# Antenna_Board_v4_3.net
KiCad netlist of a schematic drawn in EAGLE
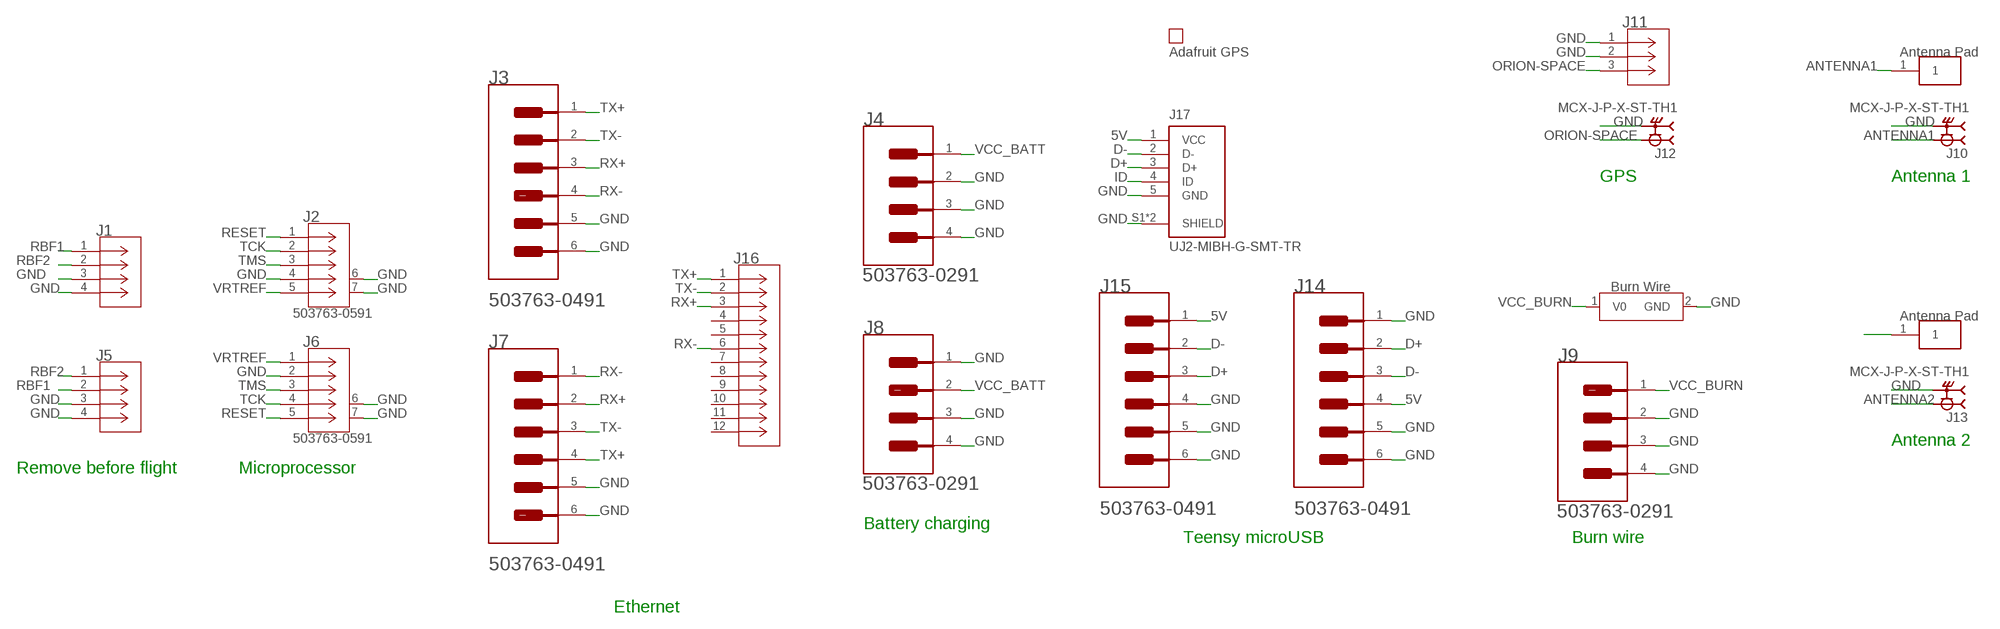
[diagram p0: schematic, sheet 1]

(export (version "E")
  (design (tool "Eeschema 10.0.6"))
  (components
    (comp (ref "GPS")
      (value "PA1010D")
      (footprint "eagle-import:PA1010D")
      (libsource (lib "eagle-import") (part "PA1010D"))
    )
    (comp (ref "J1")
      (value "5037630291")
      (footprint "eagle-import:CON_5037630291")
      (fields (field (name "COPYRIGHT") "Copyright (C) 2018 Accelerated Designs. All rights reserved"))
      (libsource (lib "eagle-import") (part "5037630291"))
    )
    (comp (ref "J2")
      (value "503763-0591")
      (footprint "eagle-import:CONN_5037630591_MOL")
      (fields (field (name "COPYRIGHT") "Copyright (C) 2018 Accelerated Designs. All rights reserved"))
      (libsource (lib "eagle-import") (part "503763-0591"))
    )
    (comp (ref "J3")
      (value "MOLEX_503763-0491MOLEX_503763-0491_0_0")
      (footprint "eagle-import:MOLEX_503763-0491_0")
      (fields
        (field (name "DIGIKEY_PART_NUMBER") "WM10655CT-ND")
        (field (name "MF") "Molex")
        (field (name "MOUSER_PART_NUMBER") "538-503763-0491")
      )
      (libsource (lib "eagle-import") (part "MOLEX_503763-0491MOLEX_503763-0491_0_0"))
    )
    (comp (ref "J4")
      (value "MOLEX_503763-0291MOLEX_503763-0291_0_0")
      (footprint "eagle-import:MOLEX_503763-0291_0")
      (fields
        (field (name "DIGIKEY_PART_NUMBER") "WM10654CT-ND")
        (field (name "MF") "Molex")
        (field (name "MOUSER_PART_NUMBER") "538-503763-0291")
      )
      (libsource (lib "eagle-import") (part "MOLEX_503763-0291MOLEX_503763-0291_0_0"))
    )
    (comp (ref "J5")
      (value "5037630291")
      (footprint "eagle-import:CON_5037630291")
      (fields (field (name "COPYRIGHT") "Copyright (C) 2018 Accelerated Designs. All rights reserved"))
      (libsource (lib "eagle-import") (part "5037630291"))
    )
    (comp (ref "J6")
      (value "503763-0591")
      (footprint "eagle-import:CONN_5037630591_MOL")
      (fields (field (name "COPYRIGHT") "Copyright (C) 2018 Accelerated Designs. All rights reserved"))
      (libsource (lib "eagle-import") (part "503763-0591"))
    )
    (comp (ref "J7")
      (value "MOLEX_503763-0491MOLEX_503763-0491_0_0")
      (footprint "eagle-import:MOLEX_503763-0491_0")
      (fields
        (field (name "DIGIKEY_PART_NUMBER") "WM10655CT-ND")
        (field (name "MF") "Molex")
        (field (name "MOUSER_PART_NUMBER") "538-503763-0491")
      )
      (libsource (lib "eagle-import") (part "MOLEX_503763-0491MOLEX_503763-0491_0_0"))
    )
    (comp (ref "J8")
      (value "MOLEX_503763-0291MOLEX_503763-0291_0_0")
      (footprint "eagle-import:MOLEX_503763-0291_0")
      (fields
        (field (name "DIGIKEY_PART_NUMBER") "WM10654CT-ND")
        (field (name "MF") "Molex")
        (field (name "MOUSER_PART_NUMBER") "538-503763-0291")
      )
      (libsource (lib "eagle-import") (part "MOLEX_503763-0291MOLEX_503763-0291_0_0"))
    )
    (comp (ref "J9")
      (value "MOLEX_503763-0291MOLEX_503763-0291_0_0")
      (footprint "eagle-import:MOLEX_503763-0291_0")
      (fields
        (field (name "DIGIKEY_PART_NUMBER") "WM10654CT-ND")
        (field (name "MF") "Molex")
        (field (name "MOUSER_PART_NUMBER") "538-503763-0291")
      )
      (libsource (lib "eagle-import") (part "MOLEX_503763-0291MOLEX_503763-0291_0_0"))
    )
    (comp (ref "J10")
      (value "MCX-J-P-X-ST-TH1")
      (footprint "eagle-import:SAMTEC_MCX-J-P-X-ST-TH1")
      (fields
        (field (name "DIGI-KEY_PART_NUMBER") "SAM8944-ND")
        (field (name "MF") "Samtec")
        (field (name "MP") "MCX-J-P-H-ST-TH1")
      )
      (libsource (lib "eagle-import") (part "MCX-J-P-X-ST-TH1"))
    )
    (comp (ref "J11")
      (value "U.FL-R-SMT-1(01)")
      (footprint "eagle-import:CONN_-SMT-1(01)")
      (fields (field (name "COPYRIGHT") "Copyright (C) 2018 Accelerated Designs. All rights reserved"))
      (libsource (lib "eagle-import") (part "U.FL-R-SMT-1(01)"))
    )
    (comp (ref "J12")
      (value "MCX-J-P-X-ST-TH1")
      (footprint "eagle-import:SAMTEC_MCX-J-P-X-ST-TH1")
      (fields
        (field (name "DIGI-KEY_PART_NUMBER") "SAM8944-ND")
        (field (name "MF") "Samtec")
        (field (name "MP") "MCX-J-P-H-ST-TH1")
      )
      (libsource (lib "eagle-import") (part "MCX-J-P-X-ST-TH1"))
    )
    (comp (ref "J13")
      (value "MCX-J-P-X-ST-TH1")
      (footprint "eagle-import:SAMTEC_MCX-J-P-X-ST-TH1")
      (fields
        (field (name "DIGI-KEY_PART_NUMBER") "SAM8944-ND")
        (field (name "MF") "Samtec")
        (field (name "MP") "MCX-J-P-H-ST-TH1")
      )
      (libsource (lib "eagle-import") (part "MCX-J-P-X-ST-TH1"))
    )
    (comp (ref "J14")
      (value "MOLEX_503763-0491MOLEX_503763-0491_0_0")
      (footprint "eagle-import:MOLEX_503763-0491_0")
      (fields
        (field (name "DIGIKEY_PART_NUMBER") "WM10655CT-ND")
        (field (name "MF") "Molex")
        (field (name "MOUSER_PART_NUMBER") "538-503763-0491")
      )
      (libsource (lib "eagle-import") (part "MOLEX_503763-0491MOLEX_503763-0491_0_0"))
    )
    (comp (ref "J15")
      (value "MOLEX_503763-0491MOLEX_503763-0491_0_0")
      (footprint "eagle-import:MOLEX_503763-0491_0")
      (fields
        (field (name "DIGIKEY_PART_NUMBER") "WM10655CT-ND")
        (field (name "MF") "Molex")
        (field (name "MOUSER_PART_NUMBER") "538-503763-0491")
      )
      (libsource (lib "eagle-import") (part "MOLEX_503763-0491MOLEX_503763-0491_0_0"))
    )
    (comp (ref "J16")
      (value "ARJM11C7-104-AB-EW2")
      (footprint "eagle-import:CONN_EW_ABR")
      (libsource (lib "eagle-import") (part "ARJM11C7-104-AB-EW2"))
    )
    (comp (ref "J17")
      (value "UJ2-MIBH-G-SMT-TR")
      (footprint "eagle-import:CUI_UJ2-MIBH-G-SMT-TR")
      (fields
        (field (name "DIGI-KEY_PART_NUMBER") "2223-UJ2-MIBH-G-SMT-TRCT-ND")
        (field (name "MF") "CUI Devices")
      )
      (libsource (lib "eagle-import") (part "UJ2-MIBH-G-SMT-TR"))
    )
    (comp (ref "U$1")
      (value "ANTENNA_PAD+HOLES")
      (footprint "eagle-import:ANTENNA_PAD+HOLES")
      (libsource (lib "eagle-import") (part "ANTENNA_PAD+HOLES"))
    )
    (comp (ref "U$2")
      (value "ANTENNA_PAD+HOLES")
      (footprint "eagle-import:ANTENNA_PAD+HOLES")
      (libsource (lib "eagle-import") (part "ANTENNA_PAD+HOLES"))
    )
    (comp (ref "U$3")
      (value "BURNWIRE")
      (footprint "eagle-import:BURNWIRE")
      (libsource (lib "eagle-import") (part "BURNWIRE"))
    )
  )
  (nets
    (net (code "1") (name "/5V") (class "Default")
      (node (ref "J14") (pin "4") (pinfunction "4_4") (pintype "passive"))
      (node (ref "J15") (pin "1") (pinfunction "1_1") (pintype "passive"))
      (node (ref "J17") (pin "1") (pinfunction "VCC_1") (pintype "power_in"))
    )
    (net (code "2") (name "/ANTENNA1") (class "Default")
      (node (ref "J10") (pin "1") (pinfunction "1_1") (pintype "passive"))
      (node (ref "U$1") (pin "1") (pinfunction "1_1") (pintype "bidirectional"))
    )
    (net (code "3") (name "/ANTENNA2") (class "Default")
      (node (ref "J13") (pin "1") (pinfunction "1_1") (pintype "passive"))
      (node (ref "U$2") (pin "1") (pinfunction "1_1") (pintype "bidirectional"))
    )
    (net (code "4") (name "/D+") (class "Default")
      (node (ref "J14") (pin "2") (pinfunction "2_2") (pintype "passive"))
      (node (ref "J15") (pin "3") (pinfunction "3_3") (pintype "passive"))
      (node (ref "J17") (pin "3") (pinfunction "D+_3") (pintype "bidirectional"))
    )
    (net (code "5") (name "/D-") (class "Default")
      (node (ref "J14") (pin "3") (pinfunction "3_3") (pintype "passive"))
      (node (ref "J15") (pin "2") (pinfunction "2_2") (pintype "passive"))
      (node (ref "J17") (pin "2") (pinfunction "D-_2") (pintype "bidirectional"))
    )
    (net (code "6") (name "/GND") (class "Default")
      (node (ref "J1") (pin "3") (pinfunction "3_3") (pintype "passive"))
      (node (ref "J1") (pin "4") (pinfunction "4_4") (pintype "passive"))
      (node (ref "J10") (pin "S1") (pinfunction "2_S1") (pintype "passive"))
      (node (ref "J10") (pin "S2") (pinfunction "2_S2") (pintype "passive"))
      (node (ref "J10") (pin "S3") (pinfunction "2_S3") (pintype "passive"))
      (node (ref "J10") (pin "S4") (pinfunction "2_S4") (pintype "passive"))
      (node (ref "J11") (pin "1") (pinfunction "1_1") (pintype "passive"))
      (node (ref "J11") (pin "2") (pinfunction "2_2") (pintype "passive"))
      (node (ref "J12") (pin "S1") (pinfunction "2_S1") (pintype "passive"))
      (node (ref "J12") (pin "S2") (pinfunction "2_S2") (pintype "passive"))
      (node (ref "J12") (pin "S3") (pinfunction "2_S3") (pintype "passive"))
      (node (ref "J12") (pin "S4") (pinfunction "2_S4") (pintype "passive"))
      (node (ref "J13") (pin "S1") (pinfunction "2_S1") (pintype "passive"))
      (node (ref "J13") (pin "S2") (pinfunction "2_S2") (pintype "passive"))
      (node (ref "J13") (pin "S3") (pinfunction "2_S3") (pintype "passive"))
      (node (ref "J13") (pin "S4") (pinfunction "2_S4") (pintype "passive"))
      (node (ref "J14") (pin "1") (pinfunction "1_1") (pintype "passive"))
      (node (ref "J14") (pin "5") (pinfunction "MNT_1_5") (pintype "passive"))
      (node (ref "J14") (pin "6") (pinfunction "MNT_2_6") (pintype "passive"))
      (node (ref "J15") (pin "4") (pinfunction "4_4") (pintype "passive"))
      (node (ref "J15") (pin "5") (pinfunction "MNT_1_5") (pintype "passive"))
      (node (ref "J15") (pin "6") (pinfunction "MNT_2_6") (pintype "passive"))
      (node (ref "J17") (pin "5") (pinfunction "GND_5") (pintype "power_in"))
      (node (ref "J17") (pin "S1") (pinfunction "SHIELD_S1") (pintype "passive"))
      (node (ref "J17") (pin "S2") (pinfunction "SHIELD_S2") (pintype "passive"))
      (node (ref "J2") (pin "4") (pinfunction "4_4") (pintype "passive"))
      (node (ref "J2") (pin "6") (pinfunction "6_6") (pintype "bidirectional"))
      (node (ref "J2") (pin "7") (pinfunction "7_7") (pintype "bidirectional"))
      (node (ref "J3") (pin "5") (pinfunction "MNT_1_5") (pintype "passive"))
      (node (ref "J3") (pin "6") (pinfunction "MNT_2_6") (pintype "passive"))
      (node (ref "J4") (pin "2") (pinfunction "2_2") (pintype "bidirectional"))
      (node (ref "J4") (pin "3") (pinfunction "MNT_1_3") (pintype "bidirectional"))
      (node (ref "J4") (pin "4") (pinfunction "MNT_2_4") (pintype "bidirectional"))
      (node (ref "J5") (pin "3") (pinfunction "3_3") (pintype "passive"))
      (node (ref "J5") (pin "4") (pinfunction "4_4") (pintype "passive"))
      (node (ref "J6") (pin "2") (pinfunction "2_2") (pintype "passive"))
      (node (ref "J6") (pin "6") (pinfunction "6_6") (pintype "bidirectional"))
      (node (ref "J6") (pin "7") (pinfunction "7_7") (pintype "bidirectional"))
      (node (ref "J7") (pin "5") (pinfunction "MNT_1_5") (pintype "passive"))
      (node (ref "J7") (pin "6") (pinfunction "MNT_2_6") (pintype "passive"))
      (node (ref "J8") (pin "1") (pinfunction "1_1") (pintype "bidirectional"))
      (node (ref "J8") (pin "3") (pinfunction "MNT_1_3") (pintype "bidirectional"))
      (node (ref "J8") (pin "4") (pinfunction "MNT_2_4") (pintype "bidirectional"))
      (node (ref "J9") (pin "2") (pinfunction "2_2") (pintype "bidirectional"))
      (node (ref "J9") (pin "3") (pinfunction "MNT_1_3") (pintype "bidirectional"))
      (node (ref "J9") (pin "4") (pinfunction "MNT_2_4") (pintype "bidirectional"))
      (node (ref "U$3") (pin "2") (pinfunction "GND_2") (pintype "bidirectional"))
    )
    (net (code "7") (name "/ID") (class "Default")
      (node (ref "J17") (pin "4") (pinfunction "ID_4") (pintype "bidirectional"))
    )
    (net (code "8") (name "/ORION-SPACE") (class "Default")
      (node (ref "J11") (pin "3") (pinfunction "3_3") (pintype "passive"))
      (node (ref "J12") (pin "1") (pinfunction "1_1") (pintype "passive"))
    )
    (net (code "9") (name "/RBF1") (class "Default")
      (node (ref "J1") (pin "1") (pinfunction "1_1") (pintype "passive"))
      (node (ref "J5") (pin "2") (pinfunction "2_2") (pintype "passive"))
    )
    (net (code "10") (name "/RBF2") (class "Default")
      (node (ref "J1") (pin "2") (pinfunction "2_2") (pintype "passive"))
      (node (ref "J5") (pin "1") (pinfunction "1_1") (pintype "passive"))
    )
    (net (code "11") (name "/RESET") (class "Default")
      (node (ref "J2") (pin "1") (pinfunction "1_1") (pintype "passive"))
      (node (ref "J6") (pin "5") (pinfunction "5_5") (pintype "passive"))
    )
    (net (code "12") (name "/RX+") (class "Default")
      (node (ref "J16") (pin "3") (pinfunction "3_3") (pintype "passive"))
      (node (ref "J3") (pin "3") (pinfunction "3_3") (pintype "passive"))
      (node (ref "J7") (pin "2") (pinfunction "2_2") (pintype "passive"))
    )
    (net (code "13") (name "/RX-") (class "Default")
      (node (ref "J16") (pin "6") (pinfunction "6_6") (pintype "passive"))
      (node (ref "J3") (pin "4") (pinfunction "4_4") (pintype "passive"))
      (node (ref "J7") (pin "1") (pinfunction "1_1") (pintype "passive"))
    )
    (net (code "14") (name "/TCK") (class "Default")
      (node (ref "J2") (pin "2") (pinfunction "2_2") (pintype "passive"))
      (node (ref "J6") (pin "4") (pinfunction "4_4") (pintype "passive"))
    )
    (net (code "15") (name "/TMS") (class "Default")
      (node (ref "J2") (pin "3") (pinfunction "3_3") (pintype "passive"))
      (node (ref "J6") (pin "3") (pinfunction "3_3") (pintype "passive"))
    )
    (net (code "16") (name "/TX+") (class "Default")
      (node (ref "J16") (pin "1") (pinfunction "1_1") (pintype "passive"))
      (node (ref "J3") (pin "1") (pinfunction "1_1") (pintype "passive"))
      (node (ref "J7") (pin "4") (pinfunction "4_4") (pintype "passive"))
    )
    (net (code "17") (name "/TX-") (class "Default")
      (node (ref "J16") (pin "2") (pinfunction "2_2") (pintype "passive"))
      (node (ref "J3") (pin "2") (pinfunction "2_2") (pintype "passive"))
      (node (ref "J7") (pin "3") (pinfunction "3_3") (pintype "passive"))
    )
    (net (code "18") (name "/VCC_BATT") (class "Default")
      (node (ref "J4") (pin "1") (pinfunction "1_1") (pintype "bidirectional"))
      (node (ref "J8") (pin "2") (pinfunction "2_2") (pintype "bidirectional"))
    )
    (net (code "19") (name "/VCC_BURN") (class "Default")
      (node (ref "J9") (pin "1") (pinfunction "1_1") (pintype "bidirectional"))
      (node (ref "U$3") (pin "1") (pinfunction "V0_1") (pintype "bidirectional"))
    )
    (net (code "20") (name "/VRTREF") (class "Default")
      (node (ref "J2") (pin "5") (pinfunction "5_5") (pintype "passive"))
      (node (ref "J6") (pin "1") (pinfunction "1_1") (pintype "passive"))
    )
    (net (code "21") (name "unconnected-(J16-Pad4)") (class "Default")
      (node (ref "J16") (pin "4") (pinfunction "4_4") (pintype "passive"))
    )
    (net (code "22") (name "unconnected-(J16-Pad5)") (class "Default")
      (node (ref "J16") (pin "5") (pinfunction "5_5") (pintype "passive"))
    )
    (net (code "23") (name "unconnected-(J16-Pad7)") (class "Default")
      (node (ref "J16") (pin "7") (pinfunction "7_7") (pintype "passive"))
    )
    (net (code "24") (name "unconnected-(J16-Pad8)") (class "Default")
      (node (ref "J16") (pin "8") (pinfunction "8_8") (pintype "passive"))
    )
    (net (code "25") (name "unconnected-(J16-Pad9)") (class "Default")
      (node (ref "J16") (pin "9") (pinfunction "9_9") (pintype "passive"))
    )
    (net (code "26") (name "unconnected-(J16-Pad10)") (class "Default")
      (node (ref "J16") (pin "10") (pinfunction "10_10") (pintype "passive"))
    )
    (net (code "27") (name "unconnected-(J16-Pad11)") (class "Default")
      (node (ref "J16") (pin "11") (pinfunction "11_11") (pintype "passive"))
    )
    (net (code "28") (name "unconnected-(J16-Pad12)") (class "Default")
      (node (ref "J16") (pin "12") (pinfunction "12_12") (pintype "passive"))
    )
  )
)
